# synth-zodiac-cancer-led.net
KiCad netlist of a schematic drawn in EAGLE
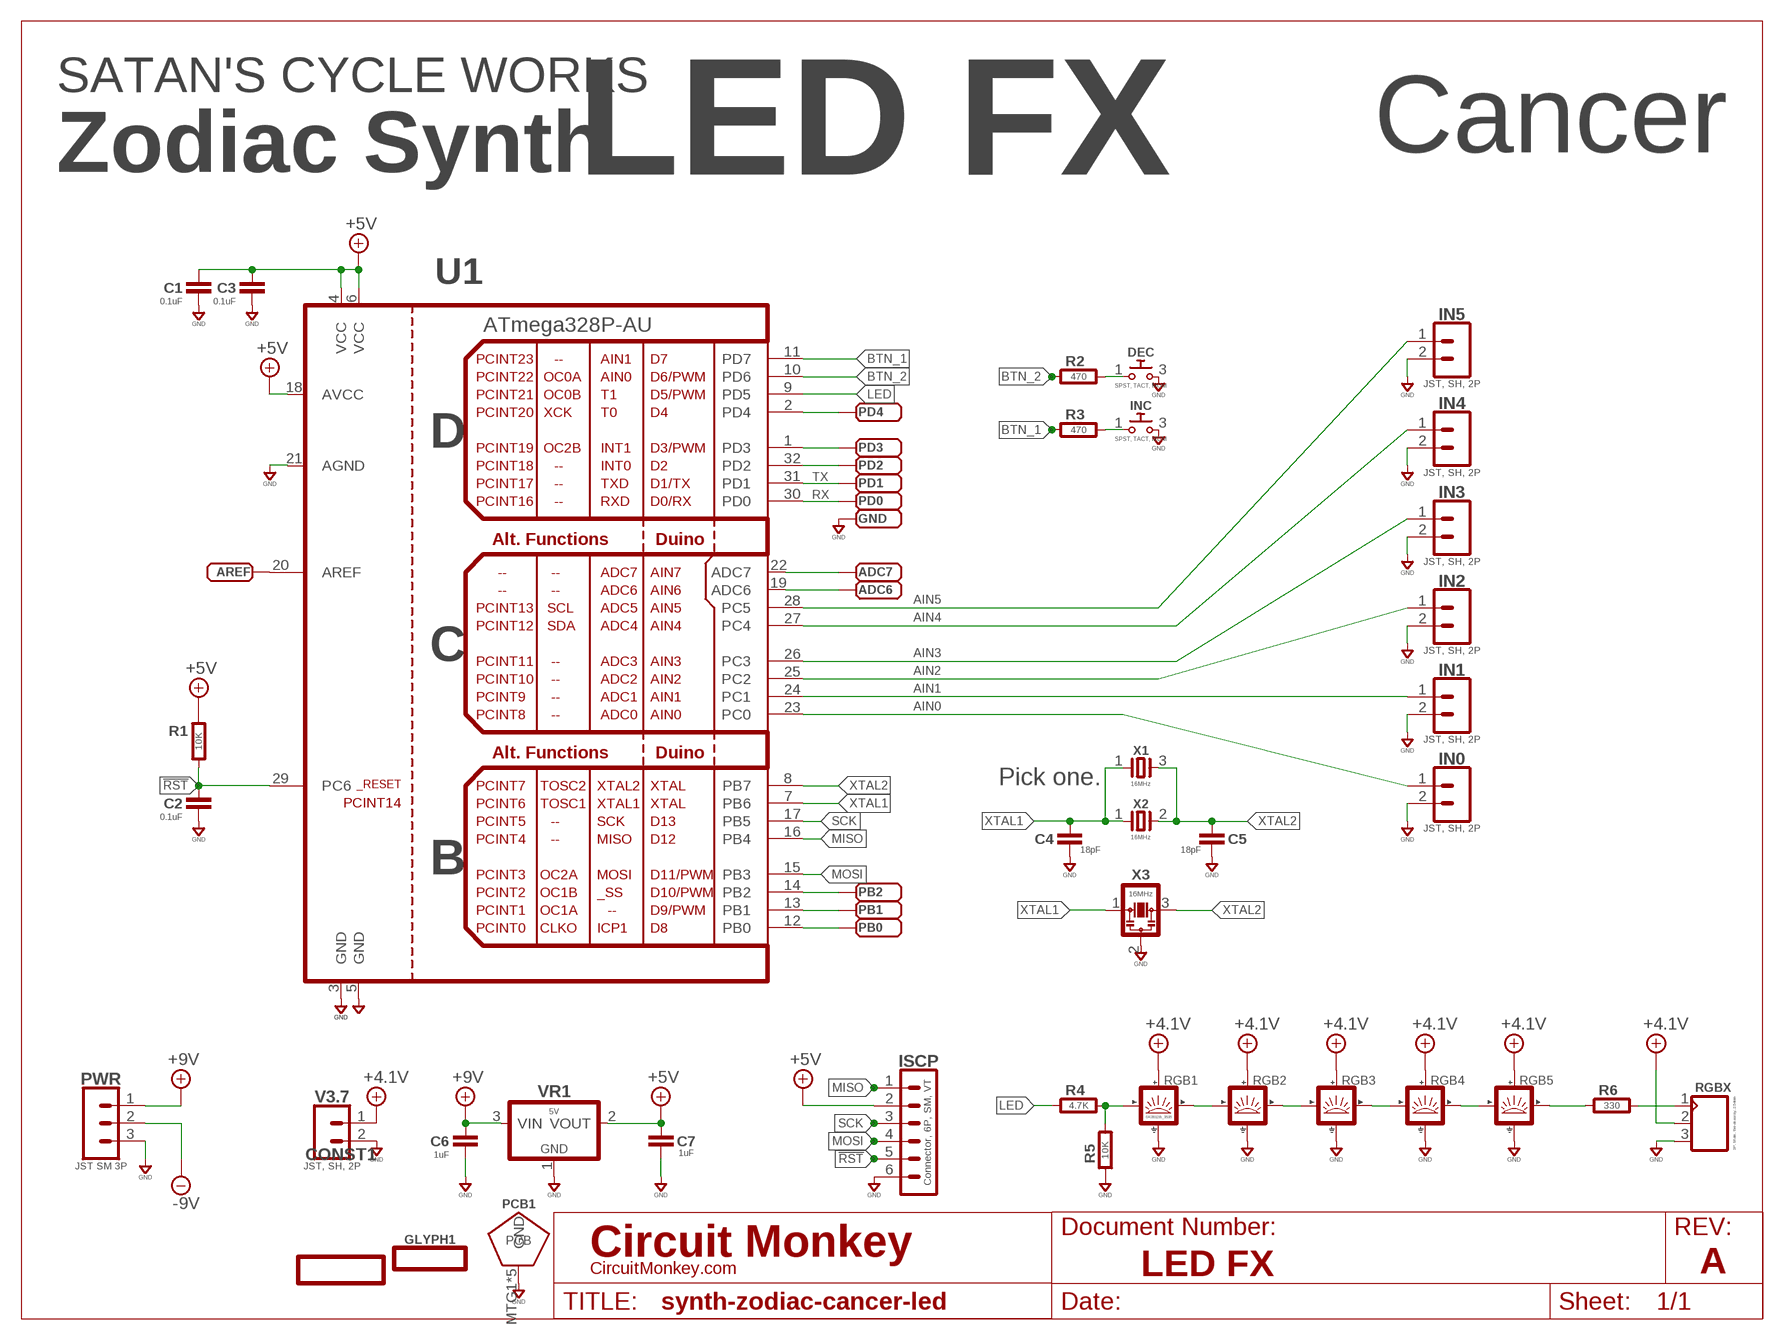
[diagram p0: schematic, sheet 1]

(export (version "E")
  (design (tool "Eeschema 10.0.6"))
  (components
    (comp (ref "ADC6")
      (value "PADSMD-050X050")
      (footprint "eagle-import:SMD-050X050")
      (libsource (lib "eagle-import") (part "PADSMD-050X050"))
    )
    (comp (ref "ADC7")
      (value "PADSMD-050X050")
      (footprint "eagle-import:SMD-050X050")
      (libsource (lib "eagle-import") (part "PADSMD-050X050"))
    )
    (comp (ref "AREF")
      (value "PADSMD-050X050")
      (footprint "eagle-import:SMD-050X050")
      (libsource (lib "eagle-import") (part "PADSMD-050X050"))
    )
    (comp (ref "C1")
      (value "0.1uF")
      (footprint "eagle-import:0603-CAP")
      (libsource (lib "eagle-import") (part "CAPACITOR0603"))
    )
    (comp (ref "C2")
      (value "0.1uF")
      (footprint "eagle-import:0603-CAP")
      (libsource (lib "eagle-import") (part "CAPACITOR0603"))
    )
    (comp (ref "C3")
      (value "0.1uF")
      (footprint "eagle-import:0603-CAP")
      (libsource (lib "eagle-import") (part "CAPACITOR0603"))
    )
    (comp (ref "C4")
      (value "18pF")
      (footprint "eagle-import:0603-CAP")
      (libsource (lib "eagle-import") (part "CAPACITOR0603"))
    )
    (comp (ref "C5")
      (value "18pF")
      (footprint "eagle-import:0603-CAP")
      (libsource (lib "eagle-import") (part "CAPACITOR0603"))
    )
    (comp (ref "C6")
      (value "1uF")
      (footprint "eagle-import:0603-CAP")
      (libsource (lib "eagle-import") (part "CAPACITOR0603"))
    )
    (comp (ref "C7")
      (value "1uF")
      (footprint "eagle-import:0603-CAP")
      (libsource (lib "eagle-import") (part "CAPACITOR0603"))
    )
    (comp (ref "CONST1")
      (value "CONSTELLATION-CANCER")
      (footprint "eagle-import:CANCER-CONST")
      (libsource (lib "eagle-import") (part "CONSTELLATION-CANCER"))
    )
    (comp (ref "DEC")
      (value "SPST, TACT, MOM")
      (footprint "eagle-import:B3FS-BACKMOUNT")
      (fields (field (name "MFR") "CK") (field (name "MPN") "B3FS"))
      (libsource (lib "eagle-import") (part "PUSHBTN-MOMB3FS-BLIND"))
    )
    (comp (ref "GLYPH1")
      (value "GLYPH-CANCER")
      (footprint "eagle-import:CANCER-GLYPH")
      (libsource (lib "eagle-import") (part "GLYPH-CANCER"))
    )
    (comp (ref "GND")
      (value "PADSMD-050X050")
      (footprint "eagle-import:SMD-050X050")
      (libsource (lib "eagle-import") (part "PADSMD-050X050"))
    )
    (comp (ref "IN0")
      (value "JST, SH, 2P")
      (footprint "eagle-import:BM02B-SRSS-TB")
      (fields (field (name "MFR") "JST") (field (name "MPN") "BMB02B-SRSS-TB"))
      (libsource (lib "eagle-import") (part "02P-SM-VT-SMT"))
    )
    (comp (ref "IN1")
      (value "JST, SH, 2P")
      (footprint "eagle-import:BM02B-SRSS-TB")
      (fields (field (name "MFR") "JST") (field (name "MPN") "BMB02B-SRSS-TB"))
      (libsource (lib "eagle-import") (part "02P-SM-VT-SMT"))
    )
    (comp (ref "IN2")
      (value "JST, SH, 2P")
      (footprint "eagle-import:BM02B-SRSS-TB")
      (fields (field (name "MFR") "JST") (field (name "MPN") "BMB02B-SRSS-TB"))
      (libsource (lib "eagle-import") (part "02P-SM-VT-SMT"))
    )
    (comp (ref "IN3")
      (value "JST, SH, 2P")
      (footprint "eagle-import:BM02B-SRSS-TB")
      (fields (field (name "MFR") "JST") (field (name "MPN") "BMB02B-SRSS-TB"))
      (libsource (lib "eagle-import") (part "02P-SM-VT-SMT"))
    )
    (comp (ref "IN4")
      (value "JST, SH, 2P")
      (footprint "eagle-import:BM02B-SRSS-TB")
      (fields (field (name "MFR") "JST") (field (name "MPN") "BMB02B-SRSS-TB"))
      (libsource (lib "eagle-import") (part "02P-SM-VT-SMT"))
    )
    (comp (ref "IN5")
      (value "JST, SH, 2P")
      (footprint "eagle-import:BM02B-SRSS-TB")
      (fields (field (name "MFR") "JST") (field (name "MPN") "BMB02B-SRSS-TB"))
      (libsource (lib "eagle-import") (part "02P-SM-VT-SMT"))
    )
    (comp (ref "INC")
      (value "SPST, TACT, MOM")
      (footprint "eagle-import:B3FS-BACKMOUNT")
      (fields (field (name "MFR") "CK") (field (name "MPN") "B3FS"))
      (libsource (lib "eagle-import") (part "PUSHBTN-MOMB3FS-BLIND"))
    )
    (comp (ref "ISCP")
      (value "Connector, 6P, SM, VT")
      (footprint "eagle-import:BM06B-SRSS-TB")
      (fields (field (name "MFR") "JST") (field (name "MPN") "BM06-SRSS-TB"))
      (libsource (lib "eagle-import") (part "06P-SM-VT-SMT"))
    )
    (comp (ref "PB0")
      (value "PADSMD-050X050")
      (footprint "eagle-import:SMD-050X050")
      (libsource (lib "eagle-import") (part "PADSMD-050X050"))
    )
    (comp (ref "PB1")
      (value "PADSMD-050X050")
      (footprint "eagle-import:SMD-050X050")
      (libsource (lib "eagle-import") (part "PADSMD-050X050"))
    )
    (comp (ref "PB2")
      (value "PADSMD-050X050")
      (footprint "eagle-import:SMD-050X050")
      (libsource (lib "eagle-import") (part "PADSMD-050X050"))
    )
    (comp (ref "PCB1")
      (value "PCB FAB")
      (footprint "eagle-import:PENTAGON-40MM-RAD")
      (libsource (lib "eagle-import") (part "PENTAGON-40R"))
    )
    (comp (ref "PD0")
      (value "PADSMD-050X050")
      (footprint "eagle-import:SMD-050X050")
      (libsource (lib "eagle-import") (part "PADSMD-050X050"))
    )
    (comp (ref "PD1")
      (value "PADSMD-050X050")
      (footprint "eagle-import:SMD-050X050")
      (libsource (lib "eagle-import") (part "PADSMD-050X050"))
    )
    (comp (ref "PD2")
      (value "PADSMD-050X050")
      (footprint "eagle-import:SMD-050X050")
      (libsource (lib "eagle-import") (part "PADSMD-050X050"))
    )
    (comp (ref "PD3")
      (value "PADSMD-050X050")
      (footprint "eagle-import:SMD-050X050")
      (libsource (lib "eagle-import") (part "PADSMD-050X050"))
    )
    (comp (ref "PD4")
      (value "PADSMD-050X050")
      (footprint "eagle-import:SMD-050X050")
      (libsource (lib "eagle-import") (part "PADSMD-050X050"))
    )
    (comp (ref "PWR")
      (value "JST SM 3P")
      (footprint "eagle-import:BM03B-SRSS-TB")
      (fields (field (name "MFR") "JST") (field (name "MPN") "BM03B-SRSS-TB"))
      (libsource (lib "eagle-import") (part "03P-SM-VT-SMT"))
    )
    (comp (ref "R1")
      (value "10K")
      (footprint "eagle-import:0603-RES")
      (libsource (lib "eagle-import") (part "RESISTOR0603"))
    )
    (comp (ref "R2")
      (value "470")
      (footprint "eagle-import:0603-RES")
      (libsource (lib "eagle-import") (part "RESISTOR0603"))
    )
    (comp (ref "R3")
      (value "470")
      (footprint "eagle-import:0603-RES")
      (libsource (lib "eagle-import") (part "RESISTOR0603"))
    )
    (comp (ref "R4")
      (value "4.7K")
      (footprint "eagle-import:0603-RES")
      (libsource (lib "eagle-import") (part "RESISTOR0603"))
    )
    (comp (ref "R5")
      (value "10K")
      (footprint "eagle-import:0603-RES")
      (libsource (lib "eagle-import") (part "RESISTOR0603"))
    )
    (comp (ref "R6")
      (value "330")
      (footprint "eagle-import:0603-RES")
      (libsource (lib "eagle-import") (part "RESISTOR0603"))
    )
    (comp (ref "RGB1")
      (value "SK2812B_3535")
      (footprint "eagle-import:SMD_3535")
      (libsource (lib "eagle-import") (part "SMART_LED3535"))
    )
    (comp (ref "RGB2")
      (value "SMART_LED4020-SIDE")
      (footprint "eagle-import:SMD_4020")
      (libsource (lib "eagle-import") (part "SMART_LED4020-SIDE"))
    )
    (comp (ref "RGB3")
      (value "SMART_LED4020-SIDE")
      (footprint "eagle-import:SMD_4020")
      (libsource (lib "eagle-import") (part "SMART_LED4020-SIDE"))
    )
    (comp (ref "RGB4")
      (value "SMART_LED4020-SIDE")
      (footprint "eagle-import:SMD_4020")
      (libsource (lib "eagle-import") (part "SMART_LED4020-SIDE"))
    )
    (comp (ref "RGB5")
      (value "SMART_LED4020-SIDE")
      (footprint "eagle-import:SMD_4020")
      (libsource (lib "eagle-import") (part "SMART_LED4020-SIDE"))
    )
    (comp (ref "RGBX")
      (value "3P, Male, Breakaway, 2.54mm")
      (footprint "eagle-import:MA03X1-EDGE-2.54MM")
      (libsource (lib "eagle-import") (part "CON_03X1-2.54MM-SMT-EDGE"))
    )
    (comp (ref "U1")
      (value "ATmega328P-AU")
      (footprint "eagle-import:TQFP-32-08")
      (fields (field (name "MFR") "Atmel") (field (name "MPN") "ATMEGA328P-AU"))
      (libsource (lib "eagle-import") (part "ATMEGA328AU"))
    )
    (comp (ref "V3.7")
      (value "JST, SH, 2P")
      (footprint "eagle-import:BM02B-SRSS-TB")
      (fields (field (name "MFR") "JST") (field (name "MPN") "BMB02B-SRSS-TB"))
      (libsource (lib "eagle-import") (part "02P-SM-VT-SMT"))
    )
    (comp (ref "VR1")
      (value "5V")
      (footprint "eagle-import:SOT-23")
      (fields (field (name "MFR") "Diodes, Inc.") (field (name "MPN") "AP7387-50SA"))
      (libsource (lib "eagle-import") (part "LDO-3P--5V-SOT23"))
    )
    (comp (ref "X1")
      (value "16MHz")
      (footprint "eagle-import:32X25")
      (fields (field (name "MFR") "Epson") (field (name "MPN") "FA-238 16.0000MB-K3"))
      (libsource (lib "eagle-import") (part "2P3.2X2.5"))
    )
    (comp (ref "X2")
      (value "16MHz")
      (footprint "eagle-import:CTS_5X3")
      (fields (field (name "MFR") "CTS") (field (name "MPN") "445C35K16M0000"))
      (libsource (lib "eagle-import") (part "2PCTS_445"))
    )
    (comp (ref "X3")
      (value "16MHz")
      (footprint "eagle-import:CSTE-RESONATOR")
      (fields (field (name "MFR") "Murata") (field (name "MPN") "CSTCE16M"))
      (libsource (lib "eagle-import") (part "RESONATOR-CSTE16"))
    )
  )
  (nets
    (net (code "1") (name "+4.1V") (class "Default")
      (node (ref "RGB1") (pin "4") (pinfunction "VDD_4") (pintype "bidirectional"))
      (node (ref "RGB2") (pin "2") (pinfunction "VDD_2") (pintype "bidirectional"))
      (node (ref "RGB3") (pin "2") (pinfunction "VDD_2") (pintype "bidirectional"))
      (node (ref "RGB4") (pin "2") (pinfunction "VDD_2") (pintype "bidirectional"))
      (node (ref "RGB5") (pin "2") (pinfunction "VDD_2") (pintype "bidirectional"))
      (node (ref "RGBX") (pin "2") (pinfunction "2_2") (pintype "passive"))
      (node (ref "V3.7") (pin "1") (pinfunction "1_1") (pintype "passive"))
    )
    (net (code "2") (name "+5V") (class "Default")
      (node (ref "C1") (pin "1") (pinfunction "1_1") (pintype "passive"))
      (node (ref "C3") (pin "1") (pinfunction "1_1") (pintype "passive"))
      (node (ref "C7") (pin "1") (pinfunction "1_1") (pintype "passive"))
      (node (ref "ISCP") (pin "2") (pinfunction "2_2") (pintype "passive"))
      (node (ref "R1") (pin "1") (pinfunction "1_1") (pintype "passive"))
      (node (ref "U1") (pin "18") (pinfunction "AVCC_18") (pintype "power_in"))
      (node (ref "U1") (pin "4") (pinfunction "VCC_4") (pintype "power_in"))
      (node (ref "U1") (pin "6") (pinfunction "VCC_6") (pintype "power_in"))
      (node (ref "VR1") (pin "2") (pinfunction "VOUT_2") (pintype "power_in"))
    )
    (net (code "3") (name "+9V") (class "Default")
      (node (ref "C6") (pin "1") (pinfunction "1_1") (pintype "passive"))
      (node (ref "PWR") (pin "1") (pinfunction "1_1") (pintype "passive"))
      (node (ref "VR1") (pin "3") (pinfunction "VIN_3") (pintype "power_in"))
    )
    (net (code "4") (name "-9V") (class "Default")
      (node (ref "PWR") (pin "2") (pinfunction "2_2") (pintype "passive"))
    )
    (net (code "5") (name "/AIN0") (class "Default")
      (node (ref "IN0") (pin "1") (pinfunction "1_1") (pintype "passive"))
      (node (ref "U1") (pin "23") (pinfunction "PC0_23") (pintype "bidirectional"))
    )
    (net (code "6") (name "/AIN1") (class "Default")
      (node (ref "IN1") (pin "1") (pinfunction "1_1") (pintype "passive"))
      (node (ref "U1") (pin "24") (pinfunction "PC1_24") (pintype "bidirectional"))
    )
    (net (code "7") (name "/AIN2") (class "Default")
      (node (ref "IN2") (pin "1") (pinfunction "1_1") (pintype "passive"))
      (node (ref "U1") (pin "25") (pinfunction "PC2_25") (pintype "bidirectional"))
    )
    (net (code "8") (name "/AIN3") (class "Default")
      (node (ref "IN3") (pin "1") (pinfunction "1_1") (pintype "passive"))
      (node (ref "U1") (pin "26") (pinfunction "PC3_26") (pintype "bidirectional"))
    )
    (net (code "9") (name "/AIN4") (class "Default")
      (node (ref "IN4") (pin "1") (pinfunction "1_1") (pintype "passive"))
      (node (ref "U1") (pin "27") (pinfunction "PC4_27") (pintype "bidirectional"))
    )
    (net (code "10") (name "/AIN5") (class "Default")
      (node (ref "IN5") (pin "1") (pinfunction "1_1") (pintype "passive"))
      (node (ref "U1") (pin "28") (pinfunction "PC5_28") (pintype "bidirectional"))
    )
    (net (code "11") (name "/RX") (class "Default")
      (node (ref "PD0") (pin "1") (pinfunction "PAD_1") (pintype "bidirectional"))
      (node (ref "U1") (pin "30") (pinfunction "PD0_30") (pintype "bidirectional"))
    )
    (net (code "12") (name "/TX") (class "Default")
      (node (ref "PD1") (pin "1") (pinfunction "PAD_1") (pintype "bidirectional"))
      (node (ref "U1") (pin "31") (pinfunction "PD1_31") (pintype "bidirectional"))
    )
    (net (code "13") (name "/~{RST}") (class "Default")
      (node (ref "C2") (pin "1") (pinfunction "1_1") (pintype "passive"))
      (node (ref "ISCP") (pin "5") (pinfunction "5_5") (pintype "passive"))
      (node (ref "R1") (pin "2") (pinfunction "2_2") (pintype "passive"))
      (node (ref "U1") (pin "29") (pinfunction "PC6_29") (pintype "bidirectional"))
    )
    (net (code "14") (name "BTN_1") (class "Default")
      (node (ref "R3") (pin "1") (pinfunction "1_1") (pintype "passive"))
      (node (ref "U1") (pin "11") (pinfunction "PD7_11") (pintype "bidirectional"))
    )
    (net (code "15") (name "BTN_2") (class "Default")
      (node (ref "R2") (pin "1") (pinfunction "1_1") (pintype "passive"))
      (node (ref "U1") (pin "10") (pinfunction "PD6_10") (pintype "bidirectional"))
    )
    (net (code "16") (name "GND") (class "Default")
      (node (ref "C1") (pin "2") (pinfunction "2_2") (pintype "passive"))
      (node (ref "C2") (pin "2") (pinfunction "2_2") (pintype "passive"))
      (node (ref "C3") (pin "2") (pinfunction "2_2") (pintype "passive"))
      (node (ref "C4") (pin "2") (pinfunction "2_2") (pintype "passive"))
      (node (ref "C5") (pin "2") (pinfunction "2_2") (pintype "passive"))
      (node (ref "C6") (pin "2") (pinfunction "2_2") (pintype "passive"))
      (node (ref "C7") (pin "2") (pinfunction "2_2") (pintype "passive"))
      (node (ref "DEC") (pin "3") (pinfunction "2_3") (pintype "passive"))
      (node (ref "GND") (pin "1") (pinfunction "PAD_1") (pintype "bidirectional"))
      (node (ref "IN0") (pin "2") (pinfunction "2_2") (pintype "passive"))
      (node (ref "IN1") (pin "2") (pinfunction "2_2") (pintype "passive"))
      (node (ref "IN2") (pin "2") (pinfunction "2_2") (pintype "passive"))
      (node (ref "IN3") (pin "2") (pinfunction "2_2") (pintype "passive"))
      (node (ref "IN4") (pin "2") (pinfunction "2_2") (pintype "passive"))
      (node (ref "IN5") (pin "2") (pinfunction "2_2") (pintype "passive"))
      (node (ref "INC") (pin "3") (pinfunction "2_3") (pintype "passive"))
      (node (ref "ISCP") (pin "6") (pinfunction "6_6") (pintype "passive"))
      (node (ref "PCB1") (pin "MTG1") (pinfunction "GND_MTG1") (pintype "bidirectional"))
      (node (ref "PCB1") (pin "MTG2") (pinfunction "GND_MTG2") (pintype "bidirectional"))
      (node (ref "PCB1") (pin "MTG3") (pinfunction "GND_MTG3") (pintype "bidirectional"))
      (node (ref "PCB1") (pin "MTG4") (pinfunction "GND_MTG4") (pintype "bidirectional"))
      (node (ref "PCB1") (pin "MTG5") (pinfunction "GND_MTG5") (pintype "bidirectional"))
      (node (ref "PWR") (pin "3") (pinfunction "3_3") (pintype "passive"))
      (node (ref "R5") (pin "1") (pinfunction "1_1") (pintype "passive"))
      (node (ref "RGB1") (pin "2") (pinfunction "GND_2") (pintype "bidirectional"))
      (node (ref "RGB2") (pin "4") (pinfunction "GND_4") (pintype "bidirectional"))
      (node (ref "RGB3") (pin "4") (pinfunction "GND_4") (pintype "bidirectional"))
      (node (ref "RGB4") (pin "4") (pinfunction "GND_4") (pintype "bidirectional"))
      (node (ref "RGB5") (pin "4") (pinfunction "GND_4") (pintype "bidirectional"))
      (node (ref "RGBX") (pin "3") (pinfunction "3_3") (pintype "passive"))
      (node (ref "U1") (pin "21") (pinfunction "AGND_21") (pintype "power_in"))
      (node (ref "U1") (pin "3") (pinfunction "GND_3") (pintype "power_in"))
      (node (ref "U1") (pin "5") (pinfunction "GND_5") (pintype "power_in"))
      (node (ref "V3.7") (pin "2") (pinfunction "2_2") (pintype "passive"))
      (node (ref "VR1") (pin "1") (pinfunction "GND_1") (pintype "power_in"))
      (node (ref "X3") (pin "2") (pinfunction "2_2") (pintype "bidirectional"))
    )
    (net (code "17") (name "LED") (class "Default")
      (node (ref "R4") (pin "1") (pinfunction "1_1") (pintype "passive"))
      (node (ref "U1") (pin "9") (pinfunction "PD5_9") (pintype "bidirectional"))
    )
    (net (code "18") (name "MISO") (class "Default")
      (node (ref "ISCP") (pin "1") (pinfunction "1_1") (pintype "passive"))
      (node (ref "U1") (pin "16") (pinfunction "PB4_16") (pintype "bidirectional"))
    )
    (net (code "19") (name "MOSI") (class "Default")
      (node (ref "ISCP") (pin "4") (pinfunction "4_4") (pintype "passive"))
      (node (ref "U1") (pin "15") (pinfunction "PB3_15") (pintype "bidirectional"))
    )
    (net (code "20") (name "Net-(ADC6-PAD)") (class "Default")
      (node (ref "ADC6") (pin "1") (pinfunction "PAD_1") (pintype "bidirectional"))
      (node (ref "U1") (pin "19") (pinfunction "ADC6_19") (pintype "bidirectional"))
    )
    (net (code "21") (name "Net-(ADC7-PAD)") (class "Default")
      (node (ref "ADC7") (pin "1") (pinfunction "PAD_1") (pintype "bidirectional"))
      (node (ref "U1") (pin "22") (pinfunction "ADC7_22") (pintype "bidirectional"))
    )
    (net (code "22") (name "Net-(AREF-PAD)") (class "Default")
      (node (ref "AREF") (pin "1") (pinfunction "PAD_1") (pintype "bidirectional"))
      (node (ref "U1") (pin "20") (pinfunction "AREF_20") (pintype "input"))
    )
    (net (code "23") (name "Net-(DEC-Pad1)") (class "Default")
      (node (ref "DEC") (pin "1") (pinfunction "1_1") (pintype "passive"))
      (node (ref "R2") (pin "2") (pinfunction "2_2") (pintype "passive"))
    )
    (net (code "24") (name "Net-(INC-Pad1)") (class "Default")
      (node (ref "INC") (pin "1") (pinfunction "1_1") (pintype "passive"))
      (node (ref "R3") (pin "2") (pinfunction "2_2") (pintype "passive"))
    )
    (net (code "25") (name "Net-(PB0-PAD)") (class "Default")
      (node (ref "PB0") (pin "1") (pinfunction "PAD_1") (pintype "bidirectional"))
      (node (ref "U1") (pin "12") (pinfunction "PB0_12") (pintype "bidirectional"))
    )
    (net (code "26") (name "Net-(PB1-PAD)") (class "Default")
      (node (ref "PB1") (pin "1") (pinfunction "PAD_1") (pintype "bidirectional"))
      (node (ref "U1") (pin "13") (pinfunction "PB1_13") (pintype "bidirectional"))
    )
    (net (code "27") (name "Net-(PB2-PAD)") (class "Default")
      (node (ref "PB2") (pin "1") (pinfunction "PAD_1") (pintype "bidirectional"))
      (node (ref "U1") (pin "14") (pinfunction "PB2_14") (pintype "bidirectional"))
    )
    (net (code "28") (name "Net-(PD2-PAD)") (class "Default")
      (node (ref "PD2") (pin "1") (pinfunction "PAD_1") (pintype "bidirectional"))
      (node (ref "U1") (pin "32") (pinfunction "PD2_32") (pintype "bidirectional"))
    )
    (net (code "29") (name "Net-(PD3-PAD)") (class "Default")
      (node (ref "PD3") (pin "1") (pinfunction "PAD_1") (pintype "bidirectional"))
      (node (ref "U1") (pin "1") (pinfunction "PD3_1") (pintype "bidirectional"))
    )
    (net (code "30") (name "Net-(PD4-PAD)") (class "Default")
      (node (ref "PD4") (pin "1") (pinfunction "PAD_1") (pintype "bidirectional"))
      (node (ref "U1") (pin "2") (pinfunction "PD4_2") (pintype "bidirectional"))
    )
    (net (code "31") (name "Net-(R6-Pad2)") (class "Default")
      (node (ref "R6") (pin "2") (pinfunction "2_2") (pintype "passive"))
      (node (ref "RGBX") (pin "1") (pinfunction "1_1") (pintype "passive"))
    )
    (net (code "32") (name "Net-(RGB1-IN)") (class "Default")
      (node (ref "R4") (pin "2") (pinfunction "2_2") (pintype "passive"))
      (node (ref "R5") (pin "2") (pinfunction "2_2") (pintype "passive"))
      (node (ref "RGB1") (pin "3") (pinfunction "IN_3") (pintype "bidirectional"))
    )
    (net (code "33") (name "Net-(RGB1-OUT)") (class "Default")
      (node (ref "RGB1") (pin "1") (pinfunction "OUT_1") (pintype "bidirectional"))
      (node (ref "RGB2") (pin "1") (pinfunction "IN_1") (pintype "bidirectional"))
    )
    (net (code "34") (name "Net-(RGB2-OUT)") (class "Default")
      (node (ref "RGB2") (pin "3") (pinfunction "OUT_3") (pintype "bidirectional"))
      (node (ref "RGB3") (pin "1") (pinfunction "IN_1") (pintype "bidirectional"))
    )
    (net (code "35") (name "Net-(RGB3-OUT)") (class "Default")
      (node (ref "RGB3") (pin "3") (pinfunction "OUT_3") (pintype "bidirectional"))
      (node (ref "RGB4") (pin "1") (pinfunction "IN_1") (pintype "bidirectional"))
    )
    (net (code "36") (name "Net-(RGB4-OUT)") (class "Default")
      (node (ref "RGB4") (pin "3") (pinfunction "OUT_3") (pintype "bidirectional"))
      (node (ref "RGB5") (pin "1") (pinfunction "IN_1") (pintype "bidirectional"))
    )
    (net (code "37") (name "Net-(RGB5-OUT)") (class "Default")
      (node (ref "R6") (pin "1") (pinfunction "1_1") (pintype "passive"))
      (node (ref "RGB5") (pin "3") (pinfunction "OUT_3") (pintype "bidirectional"))
    )
    (net (code "38") (name "SCK") (class "Default")
      (node (ref "ISCP") (pin "3") (pinfunction "3_3") (pintype "passive"))
      (node (ref "U1") (pin "17") (pinfunction "PB5_17") (pintype "bidirectional"))
    )
    (net (code "39") (name "XTAL1") (class "Default")
      (node (ref "C4") (pin "1") (pinfunction "1_1") (pintype "passive"))
      (node (ref "U1") (pin "7") (pinfunction "PB6_7") (pintype "bidirectional"))
      (node (ref "X1") (pin "1") (pinfunction "P$1_1") (pintype "passive"))
      (node (ref "X2") (pin "1") (pinfunction "P$1_1") (pintype "passive"))
      (node (ref "X3") (pin "1") (pinfunction "1_1") (pintype "bidirectional"))
    )
    (net (code "40") (name "XTAL2") (class "Default")
      (node (ref "C5") (pin "1") (pinfunction "1_1") (pintype "passive"))
      (node (ref "U1") (pin "8") (pinfunction "PB7_8") (pintype "bidirectional"))
      (node (ref "X1") (pin "3") (pinfunction "P$2_3") (pintype "passive"))
      (node (ref "X2") (pin "2") (pinfunction "P$2_2") (pintype "passive"))
      (node (ref "X3") (pin "3") (pinfunction "3_3") (pintype "bidirectional"))
    )
  )
)
